# MF_badge_2021_protoshield_ver_A.net
KiCad netlist of a schematic drawn in EAGLE
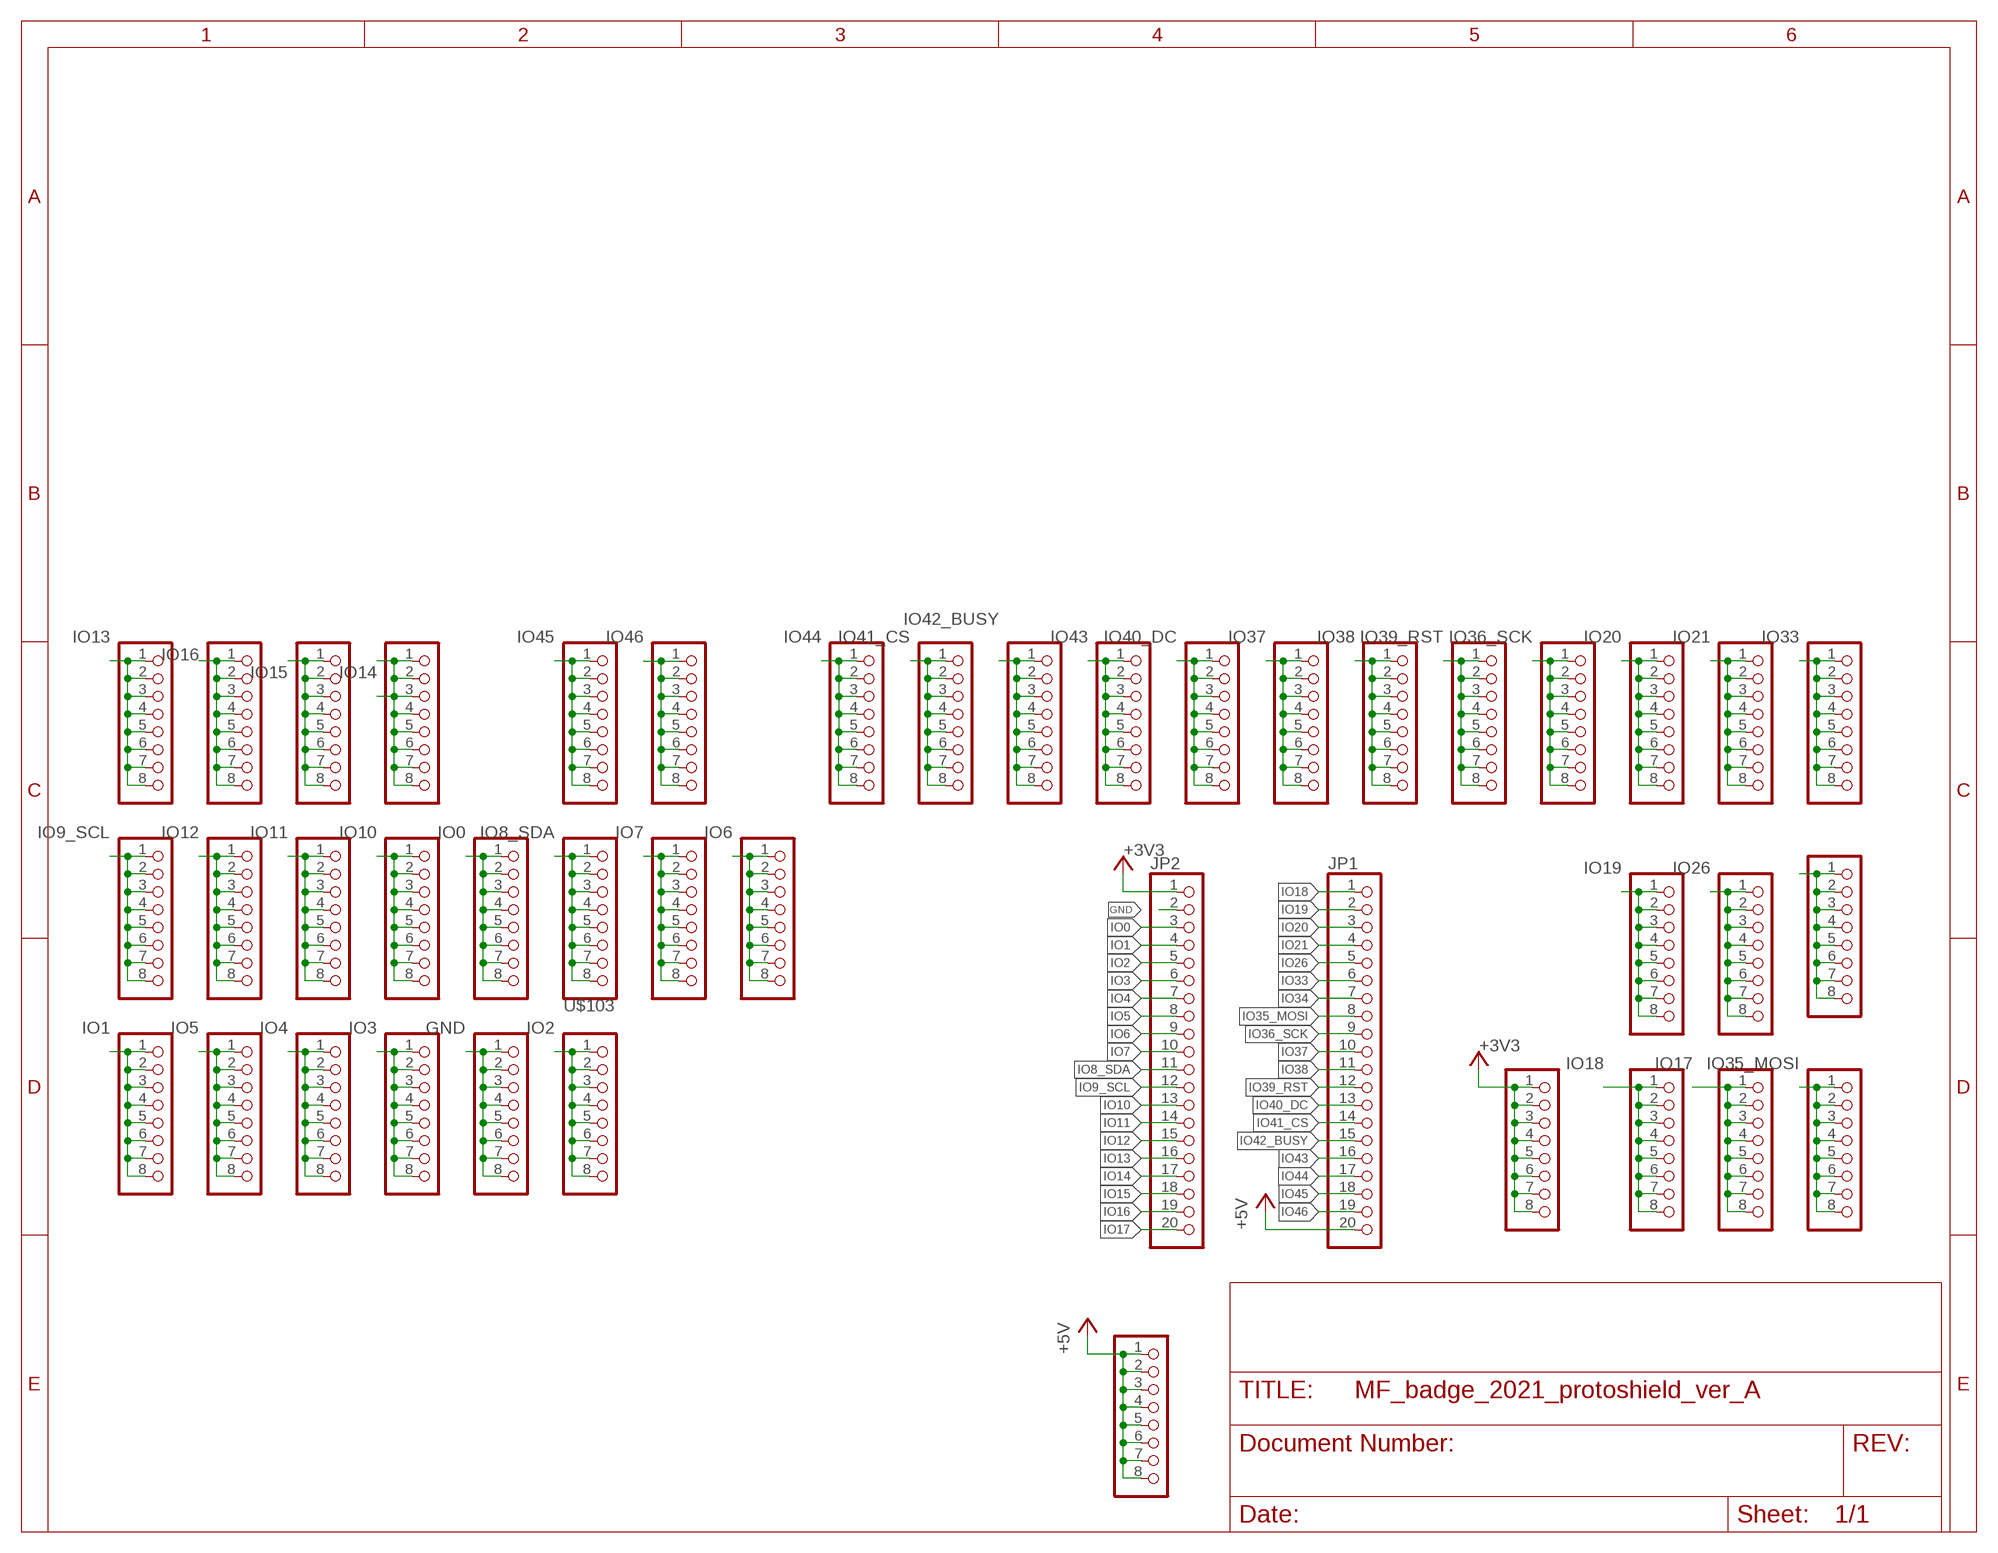
[diagram p0: schematic, sheet 1]

(export (version "E")
  (design (tool "Eeschema 10.0.6"))
  (components
    (comp (ref "JP1")
      (value "PINHD-1X20_CLEANBIG")
      (footprint "eagle-import:1X20-CLEANBIG")
      (libsource (lib "eagle-import") (part "PINHD-1X20_CLEANBIG"))
    )
    (comp (ref "JP2")
      (value "PINHD-1X20_CLEANBIG")
      (footprint "eagle-import:1X20-CLEANBIG")
      (libsource (lib "eagle-import") (part "PINHD-1X20_CLEANBIG"))
    )
    (comp (ref "U$1")
      (value "PINHD-1X8CLEANBIG")
      (footprint "eagle-import:1X08-CLEANBIG")
      (libsource (lib "eagle-import") (part "PINHD-1X8CLEANBIG"))
    )
    (comp (ref "U$5")
      (value "PINHD-1X8CLEANBIG")
      (footprint "eagle-import:1X08-CLEANBIG")
      (libsource (lib "eagle-import") (part "PINHD-1X8CLEANBIG"))
    )
    (comp (ref "U$7")
      (value "PINHD-1X8CLEANBIG")
      (footprint "eagle-import:1X08-CLEANBIG")
      (libsource (lib "eagle-import") (part "PINHD-1X8CLEANBIG"))
    )
    (comp (ref "U$8")
      (value "PINHD-1X8CLEANBIG")
      (footprint "eagle-import:1X08-CLEANBIG")
      (libsource (lib "eagle-import") (part "PINHD-1X8CLEANBIG"))
    )
    (comp (ref "U$9")
      (value "PINHD-1X8CLEANBIG")
      (footprint "eagle-import:1X08-CLEANBIG")
      (libsource (lib "eagle-import") (part "PINHD-1X8CLEANBIG"))
    )
    (comp (ref "U$10")
      (value "PINHD-1X8CLEANBIG")
      (footprint "eagle-import:1X08-CLEANBIG")
      (libsource (lib "eagle-import") (part "PINHD-1X8CLEANBIG"))
    )
    (comp (ref "U$11")
      (value "PINHD-1X8CLEANBIG")
      (footprint "eagle-import:1X08-CLEANBIG")
      (libsource (lib "eagle-import") (part "PINHD-1X8CLEANBIG"))
    )
    (comp (ref "U$12")
      (value "PINHD-1X8CLEANBIG")
      (footprint "eagle-import:1X08-CLEANBIG")
      (libsource (lib "eagle-import") (part "PINHD-1X8CLEANBIG"))
    )
    (comp (ref "U$13")
      (value "PINHD-1X8CLEANBIG")
      (footprint "eagle-import:1X08-CLEANBIG")
      (libsource (lib "eagle-import") (part "PINHD-1X8CLEANBIG"))
    )
    (comp (ref "U$14")
      (value "PINHD-1X8CLEANBIG")
      (footprint "eagle-import:1X08-CLEANBIG")
      (libsource (lib "eagle-import") (part "PINHD-1X8CLEANBIG"))
    )
    (comp (ref "U$15")
      (value "PINHD-1X8CLEANBIG")
      (footprint "eagle-import:1X08-CLEANBIG")
      (libsource (lib "eagle-import") (part "PINHD-1X8CLEANBIG"))
    )
    (comp (ref "U$36")
      (value "PINHD-1X8CLEANBIG")
      (footprint "eagle-import:1X08-CLEANBIG")
      (libsource (lib "eagle-import") (part "PINHD-1X8CLEANBIG"))
    )
    (comp (ref "U$52")
      (value "PINHD-1X8CLEANBIG")
      (footprint "eagle-import:1X08-CLEANBIG")
      (libsource (lib "eagle-import") (part "PINHD-1X8CLEANBIG"))
    )
    (comp (ref "U$53")
      (value "PINHD-1X8CLEANBIG")
      (footprint "eagle-import:1X08-CLEANBIG")
      (libsource (lib "eagle-import") (part "PINHD-1X8CLEANBIG"))
    )
    (comp (ref "U$54")
      (value "PINHD-1X8CLEANBIG")
      (footprint "eagle-import:1X08-CLEANBIG")
      (libsource (lib "eagle-import") (part "PINHD-1X8CLEANBIG"))
    )
    (comp (ref "U$55")
      (value "PINHD-1X8CLEANBIG")
      (footprint "eagle-import:1X08-CLEANBIG")
      (libsource (lib "eagle-import") (part "PINHD-1X8CLEANBIG"))
    )
    (comp (ref "U$56")
      (value "PINHD-1X8CLEANBIG")
      (footprint "eagle-import:1X08-CLEANBIG")
      (libsource (lib "eagle-import") (part "PINHD-1X8CLEANBIG"))
    )
    (comp (ref "U$61")
      (value "PINHD-1X8CLEANBIG")
      (footprint "eagle-import:1X08-CLEANBIG")
      (libsource (lib "eagle-import") (part "PINHD-1X8CLEANBIG"))
    )
    (comp (ref "U$62")
      (value "PINHD-1X8CLEANBIG")
      (footprint "eagle-import:1X08-CLEANBIG")
      (libsource (lib "eagle-import") (part "PINHD-1X8CLEANBIG"))
    )
    (comp (ref "U$63")
      (value "PINHD-1X8CLEANBIG")
      (footprint "eagle-import:1X08-CLEANBIG")
      (libsource (lib "eagle-import") (part "PINHD-1X8CLEANBIG"))
    )
    (comp (ref "U$64")
      (value "PINHD-1X8CLEANBIG")
      (footprint "eagle-import:1X08-CLEANBIG")
      (libsource (lib "eagle-import") (part "PINHD-1X8CLEANBIG"))
    )
    (comp (ref "U$102")
      (value "PINHD-1X8CLEANBIG")
      (footprint "eagle-import:1X08-CLEANBIG")
      (libsource (lib "eagle-import") (part "PINHD-1X8CLEANBIG"))
    )
    (comp (ref "U$103")
      (value "PINHD-1X8CLEANBIG")
      (footprint "eagle-import:1X08-CLEANBIG")
      (libsource (lib "eagle-import") (part "PINHD-1X8CLEANBIG"))
    )
    (comp (ref "U$104")
      (value "PINHD-1X8CLEANBIG")
      (footprint "eagle-import:1X08-CLEANBIG")
      (libsource (lib "eagle-import") (part "PINHD-1X8CLEANBIG"))
    )
    (comp (ref "U$105")
      (value "PINHD-1X8CLEANBIG")
      (footprint "eagle-import:1X08-CLEANBIG")
      (libsource (lib "eagle-import") (part "PINHD-1X8CLEANBIG"))
    )
    (comp (ref "U$106")
      (value "PINHD-1X8CLEANBIG")
      (footprint "eagle-import:1X08-CLEANBIG")
      (libsource (lib "eagle-import") (part "PINHD-1X8CLEANBIG"))
    )
    (comp (ref "U$107")
      (value "PINHD-1X8CLEANBIG")
      (footprint "eagle-import:1X08-CLEANBIG")
      (libsource (lib "eagle-import") (part "PINHD-1X8CLEANBIG"))
    )
    (comp (ref "U$108")
      (value "PINHD-1X8CLEANBIG")
      (footprint "eagle-import:1X08-CLEANBIG")
      (libsource (lib "eagle-import") (part "PINHD-1X8CLEANBIG"))
    )
    (comp (ref "U$109")
      (value "PINHD-1X8CLEANBIG")
      (footprint "eagle-import:1X08-CLEANBIG")
      (libsource (lib "eagle-import") (part "PINHD-1X8CLEANBIG"))
    )
    (comp (ref "U$110")
      (value "PINHD-1X8CLEANBIG")
      (footprint "eagle-import:1X08-CLEANBIG")
      (libsource (lib "eagle-import") (part "PINHD-1X8CLEANBIG"))
    )
    (comp (ref "U$111")
      (value "PINHD-1X8CLEANBIG")
      (footprint "eagle-import:1X08-CLEANBIG")
      (libsource (lib "eagle-import") (part "PINHD-1X8CLEANBIG"))
    )
    (comp (ref "U$112")
      (value "PINHD-1X8CLEANBIG")
      (footprint "eagle-import:1X08-CLEANBIG")
      (libsource (lib "eagle-import") (part "PINHD-1X8CLEANBIG"))
    )
    (comp (ref "U$113")
      (value "PINHD-1X8CLEANBIG")
      (footprint "eagle-import:1X08-CLEANBIG")
      (libsource (lib "eagle-import") (part "PINHD-1X8CLEANBIG"))
    )
    (comp (ref "U$114")
      (value "PINHD-1X8CLEANBIG")
      (footprint "eagle-import:1X08-CLEANBIG")
      (libsource (lib "eagle-import") (part "PINHD-1X8CLEANBIG"))
    )
    (comp (ref "U$115")
      (value "PINHD-1X8CLEANBIG")
      (footprint "eagle-import:1X08-CLEANBIG")
      (libsource (lib "eagle-import") (part "PINHD-1X8CLEANBIG"))
    )
    (comp (ref "U$116")
      (value "PINHD-1X8CLEANBIG")
      (footprint "eagle-import:1X08-CLEANBIG")
      (libsource (lib "eagle-import") (part "PINHD-1X8CLEANBIG"))
    )
    (comp (ref "U$117")
      (value "PINHD-1X8CLEANBIG")
      (footprint "eagle-import:1X08-CLEANBIG")
      (libsource (lib "eagle-import") (part "PINHD-1X8CLEANBIG"))
    )
    (comp (ref "U$118")
      (value "PINHD-1X8CLEANBIG")
      (footprint "eagle-import:1X08-CLEANBIG")
      (libsource (lib "eagle-import") (part "PINHD-1X8CLEANBIG"))
    )
    (comp (ref "U$119")
      (value "PINHD-1X8CLEANBIG")
      (footprint "eagle-import:1X08-CLEANBIG")
      (libsource (lib "eagle-import") (part "PINHD-1X8CLEANBIG"))
    )
    (comp (ref "U$120")
      (value "PINHD-1X8CLEANBIG")
      (footprint "eagle-import:1X08-CLEANBIG")
      (libsource (lib "eagle-import") (part "PINHD-1X8CLEANBIG"))
    )
  )
  (nets
    (net (code "1") (name "+3V3") (class "Default")
      (node (ref "JP2") (pin "1") (pinfunction "1_1") (pintype "passive"))
      (node (ref "U$1") (pin "1") (pinfunction "1_1") (pintype "passive"))
      (node (ref "U$1") (pin "2") (pinfunction "2_2") (pintype "passive"))
      (node (ref "U$1") (pin "3") (pinfunction "3_3") (pintype "passive"))
      (node (ref "U$1") (pin "4") (pinfunction "4_4") (pintype "passive"))
      (node (ref "U$1") (pin "5") (pinfunction "5_5") (pintype "passive"))
      (node (ref "U$1") (pin "6") (pinfunction "6_6") (pintype "passive"))
      (node (ref "U$1") (pin "7") (pinfunction "7_7") (pintype "passive"))
      (node (ref "U$1") (pin "8") (pinfunction "8_8") (pintype "passive"))
    )
    (net (code "2") (name "+5V") (class "Default")
      (node (ref "JP1") (pin "20") (pinfunction "20_20") (pintype "passive"))
      (node (ref "U$102") (pin "1") (pinfunction "1_1") (pintype "passive"))
      (node (ref "U$102") (pin "2") (pinfunction "2_2") (pintype "passive"))
      (node (ref "U$102") (pin "3") (pinfunction "3_3") (pintype "passive"))
      (node (ref "U$102") (pin "4") (pinfunction "4_4") (pintype "passive"))
      (node (ref "U$102") (pin "5") (pinfunction "5_5") (pintype "passive"))
      (node (ref "U$102") (pin "6") (pinfunction "6_6") (pintype "passive"))
      (node (ref "U$102") (pin "7") (pinfunction "7_7") (pintype "passive"))
      (node (ref "U$102") (pin "8") (pinfunction "8_8") (pintype "passive"))
    )
    (net (code "3") (name "GND") (class "Default")
      (node (ref "JP2") (pin "2") (pinfunction "2_2") (pintype "passive"))
      (node (ref "U$120") (pin "1") (pinfunction "1_1") (pintype "passive"))
      (node (ref "U$120") (pin "2") (pinfunction "2_2") (pintype "passive"))
      (node (ref "U$120") (pin "3") (pinfunction "3_3") (pintype "passive"))
      (node (ref "U$120") (pin "4") (pinfunction "4_4") (pintype "passive"))
      (node (ref "U$120") (pin "5") (pinfunction "5_5") (pintype "passive"))
      (node (ref "U$120") (pin "6") (pinfunction "6_6") (pintype "passive"))
      (node (ref "U$120") (pin "7") (pinfunction "7_7") (pintype "passive"))
      (node (ref "U$120") (pin "8") (pinfunction "8_8") (pintype "passive"))
    )
    (net (code "4") (name "IO0") (class "Default")
      (node (ref "JP2") (pin "3") (pinfunction "3_3") (pintype "passive"))
      (node (ref "U$115") (pin "1") (pinfunction "1_1") (pintype "passive"))
      (node (ref "U$115") (pin "2") (pinfunction "2_2") (pintype "passive"))
      (node (ref "U$115") (pin "3") (pinfunction "3_3") (pintype "passive"))
      (node (ref "U$115") (pin "4") (pinfunction "4_4") (pintype "passive"))
      (node (ref "U$115") (pin "5") (pinfunction "5_5") (pintype "passive"))
      (node (ref "U$115") (pin "6") (pinfunction "6_6") (pintype "passive"))
      (node (ref "U$115") (pin "7") (pinfunction "7_7") (pintype "passive"))
      (node (ref "U$115") (pin "8") (pinfunction "8_8") (pintype "passive"))
    )
    (net (code "5") (name "IO1") (class "Default")
      (node (ref "JP2") (pin "4") (pinfunction "4_4") (pintype "passive"))
      (node (ref "U$119") (pin "1") (pinfunction "1_1") (pintype "passive"))
      (node (ref "U$119") (pin "2") (pinfunction "2_2") (pintype "passive"))
      (node (ref "U$119") (pin "3") (pinfunction "3_3") (pintype "passive"))
      (node (ref "U$119") (pin "4") (pinfunction "4_4") (pintype "passive"))
      (node (ref "U$119") (pin "5") (pinfunction "5_5") (pintype "passive"))
      (node (ref "U$119") (pin "6") (pinfunction "6_6") (pintype "passive"))
      (node (ref "U$119") (pin "7") (pinfunction "7_7") (pintype "passive"))
      (node (ref "U$119") (pin "8") (pinfunction "8_8") (pintype "passive"))
    )
    (net (code "6") (name "IO2") (class "Default")
      (node (ref "JP2") (pin "5") (pinfunction "5_5") (pintype "passive"))
      (node (ref "U$103") (pin "1") (pinfunction "1_1") (pintype "passive"))
      (node (ref "U$103") (pin "2") (pinfunction "2_2") (pintype "passive"))
      (node (ref "U$103") (pin "3") (pinfunction "3_3") (pintype "passive"))
      (node (ref "U$103") (pin "4") (pinfunction "4_4") (pintype "passive"))
      (node (ref "U$103") (pin "5") (pinfunction "5_5") (pintype "passive"))
      (node (ref "U$103") (pin "6") (pinfunction "6_6") (pintype "passive"))
      (node (ref "U$103") (pin "7") (pinfunction "7_7") (pintype "passive"))
      (node (ref "U$103") (pin "8") (pinfunction "8_8") (pintype "passive"))
    )
    (net (code "7") (name "IO3") (class "Default")
      (node (ref "JP2") (pin "6") (pinfunction "6_6") (pintype "passive"))
      (node (ref "U$118") (pin "1") (pinfunction "1_1") (pintype "passive"))
      (node (ref "U$118") (pin "2") (pinfunction "2_2") (pintype "passive"))
      (node (ref "U$118") (pin "3") (pinfunction "3_3") (pintype "passive"))
      (node (ref "U$118") (pin "4") (pinfunction "4_4") (pintype "passive"))
      (node (ref "U$118") (pin "5") (pinfunction "5_5") (pintype "passive"))
      (node (ref "U$118") (pin "6") (pinfunction "6_6") (pintype "passive"))
      (node (ref "U$118") (pin "7") (pinfunction "7_7") (pintype "passive"))
      (node (ref "U$118") (pin "8") (pinfunction "8_8") (pintype "passive"))
    )
    (net (code "8") (name "IO4") (class "Default")
      (node (ref "JP2") (pin "7") (pinfunction "7_7") (pintype "passive"))
      (node (ref "U$117") (pin "1") (pinfunction "1_1") (pintype "passive"))
      (node (ref "U$117") (pin "2") (pinfunction "2_2") (pintype "passive"))
      (node (ref "U$117") (pin "3") (pinfunction "3_3") (pintype "passive"))
      (node (ref "U$117") (pin "4") (pinfunction "4_4") (pintype "passive"))
      (node (ref "U$117") (pin "5") (pinfunction "5_5") (pintype "passive"))
      (node (ref "U$117") (pin "6") (pinfunction "6_6") (pintype "passive"))
      (node (ref "U$117") (pin "7") (pinfunction "7_7") (pintype "passive"))
      (node (ref "U$117") (pin "8") (pinfunction "8_8") (pintype "passive"))
    )
    (net (code "9") (name "IO5") (class "Default")
      (node (ref "JP2") (pin "8") (pinfunction "8_8") (pintype "passive"))
      (node (ref "U$116") (pin "1") (pinfunction "1_1") (pintype "passive"))
      (node (ref "U$116") (pin "2") (pinfunction "2_2") (pintype "passive"))
      (node (ref "U$116") (pin "3") (pinfunction "3_3") (pintype "passive"))
      (node (ref "U$116") (pin "4") (pinfunction "4_4") (pintype "passive"))
      (node (ref "U$116") (pin "5") (pinfunction "5_5") (pintype "passive"))
      (node (ref "U$116") (pin "6") (pinfunction "6_6") (pintype "passive"))
      (node (ref "U$116") (pin "7") (pinfunction "7_7") (pintype "passive"))
      (node (ref "U$116") (pin "8") (pinfunction "8_8") (pintype "passive"))
    )
    (net (code "10") (name "IO6") (class "Default")
      (node (ref "JP2") (pin "9") (pinfunction "9_9") (pintype "passive"))
      (node (ref "U$114") (pin "1") (pinfunction "1_1") (pintype "passive"))
      (node (ref "U$114") (pin "2") (pinfunction "2_2") (pintype "passive"))
      (node (ref "U$114") (pin "3") (pinfunction "3_3") (pintype "passive"))
      (node (ref "U$114") (pin "4") (pinfunction "4_4") (pintype "passive"))
      (node (ref "U$114") (pin "5") (pinfunction "5_5") (pintype "passive"))
      (node (ref "U$114") (pin "6") (pinfunction "6_6") (pintype "passive"))
      (node (ref "U$114") (pin "7") (pinfunction "7_7") (pintype "passive"))
      (node (ref "U$114") (pin "8") (pinfunction "8_8") (pintype "passive"))
    )
    (net (code "11") (name "IO7") (class "Default")
      (node (ref "JP2") (pin "10") (pinfunction "10_10") (pintype "passive"))
      (node (ref "U$113") (pin "1") (pinfunction "1_1") (pintype "passive"))
      (node (ref "U$113") (pin "2") (pinfunction "2_2") (pintype "passive"))
      (node (ref "U$113") (pin "3") (pinfunction "3_3") (pintype "passive"))
      (node (ref "U$113") (pin "4") (pinfunction "4_4") (pintype "passive"))
      (node (ref "U$113") (pin "5") (pinfunction "5_5") (pintype "passive"))
      (node (ref "U$113") (pin "6") (pinfunction "6_6") (pintype "passive"))
      (node (ref "U$113") (pin "7") (pinfunction "7_7") (pintype "passive"))
      (node (ref "U$113") (pin "8") (pinfunction "8_8") (pintype "passive"))
    )
    (net (code "12") (name "IO8_SDA") (class "Default")
      (node (ref "JP2") (pin "11") (pinfunction "11_11") (pintype "passive"))
      (node (ref "U$112") (pin "1") (pinfunction "1_1") (pintype "passive"))
      (node (ref "U$112") (pin "2") (pinfunction "2_2") (pintype "passive"))
      (node (ref "U$112") (pin "3") (pinfunction "3_3") (pintype "passive"))
      (node (ref "U$112") (pin "4") (pinfunction "4_4") (pintype "passive"))
      (node (ref "U$112") (pin "5") (pinfunction "5_5") (pintype "passive"))
      (node (ref "U$112") (pin "6") (pinfunction "6_6") (pintype "passive"))
      (node (ref "U$112") (pin "7") (pinfunction "7_7") (pintype "passive"))
      (node (ref "U$112") (pin "8") (pinfunction "8_8") (pintype "passive"))
    )
    (net (code "13") (name "IO9_SCL") (class "Default")
      (node (ref "JP2") (pin "12") (pinfunction "12_12") (pintype "passive"))
      (node (ref "U$111") (pin "1") (pinfunction "1_1") (pintype "passive"))
      (node (ref "U$111") (pin "2") (pinfunction "2_2") (pintype "passive"))
      (node (ref "U$111") (pin "3") (pinfunction "3_3") (pintype "passive"))
      (node (ref "U$111") (pin "4") (pinfunction "4_4") (pintype "passive"))
      (node (ref "U$111") (pin "5") (pinfunction "5_5") (pintype "passive"))
      (node (ref "U$111") (pin "6") (pinfunction "6_6") (pintype "passive"))
      (node (ref "U$111") (pin "7") (pinfunction "7_7") (pintype "passive"))
      (node (ref "U$111") (pin "8") (pinfunction "8_8") (pintype "passive"))
    )
    (net (code "14") (name "IO10") (class "Default")
      (node (ref "JP2") (pin "13") (pinfunction "13_13") (pintype "passive"))
      (node (ref "U$110") (pin "1") (pinfunction "1_1") (pintype "passive"))
      (node (ref "U$110") (pin "2") (pinfunction "2_2") (pintype "passive"))
      (node (ref "U$110") (pin "3") (pinfunction "3_3") (pintype "passive"))
      (node (ref "U$110") (pin "4") (pinfunction "4_4") (pintype "passive"))
      (node (ref "U$110") (pin "5") (pinfunction "5_5") (pintype "passive"))
      (node (ref "U$110") (pin "6") (pinfunction "6_6") (pintype "passive"))
      (node (ref "U$110") (pin "7") (pinfunction "7_7") (pintype "passive"))
      (node (ref "U$110") (pin "8") (pinfunction "8_8") (pintype "passive"))
    )
    (net (code "15") (name "IO11") (class "Default")
      (node (ref "JP2") (pin "14") (pinfunction "14_14") (pintype "passive"))
      (node (ref "U$109") (pin "1") (pinfunction "1_1") (pintype "passive"))
      (node (ref "U$109") (pin "2") (pinfunction "2_2") (pintype "passive"))
      (node (ref "U$109") (pin "3") (pinfunction "3_3") (pintype "passive"))
      (node (ref "U$109") (pin "4") (pinfunction "4_4") (pintype "passive"))
      (node (ref "U$109") (pin "5") (pinfunction "5_5") (pintype "passive"))
      (node (ref "U$109") (pin "6") (pinfunction "6_6") (pintype "passive"))
      (node (ref "U$109") (pin "7") (pinfunction "7_7") (pintype "passive"))
      (node (ref "U$109") (pin "8") (pinfunction "8_8") (pintype "passive"))
    )
    (net (code "16") (name "IO12") (class "Default")
      (node (ref "JP2") (pin "15") (pinfunction "15_15") (pintype "passive"))
      (node (ref "U$108") (pin "1") (pinfunction "1_1") (pintype "passive"))
      (node (ref "U$108") (pin "2") (pinfunction "2_2") (pintype "passive"))
      (node (ref "U$108") (pin "3") (pinfunction "3_3") (pintype "passive"))
      (node (ref "U$108") (pin "4") (pinfunction "4_4") (pintype "passive"))
      (node (ref "U$108") (pin "5") (pinfunction "5_5") (pintype "passive"))
      (node (ref "U$108") (pin "6") (pinfunction "6_6") (pintype "passive"))
      (node (ref "U$108") (pin "7") (pinfunction "7_7") (pintype "passive"))
      (node (ref "U$108") (pin "8") (pinfunction "8_8") (pintype "passive"))
    )
    (net (code "17") (name "IO13") (class "Default")
      (node (ref "JP2") (pin "16") (pinfunction "16_16") (pintype "passive"))
      (node (ref "U$107") (pin "1") (pinfunction "1_1") (pintype "passive"))
      (node (ref "U$107") (pin "2") (pinfunction "2_2") (pintype "passive"))
      (node (ref "U$107") (pin "3") (pinfunction "3_3") (pintype "passive"))
      (node (ref "U$107") (pin "4") (pinfunction "4_4") (pintype "passive"))
      (node (ref "U$107") (pin "5") (pinfunction "5_5") (pintype "passive"))
      (node (ref "U$107") (pin "6") (pinfunction "6_6") (pintype "passive"))
      (node (ref "U$107") (pin "7") (pinfunction "7_7") (pintype "passive"))
      (node (ref "U$107") (pin "8") (pinfunction "8_8") (pintype "passive"))
    )
    (net (code "18") (name "IO14") (class "Default")
      (node (ref "JP2") (pin "17") (pinfunction "17_17") (pintype "passive"))
      (node (ref "U$106") (pin "1") (pinfunction "1_1") (pintype "passive"))
      (node (ref "U$106") (pin "2") (pinfunction "2_2") (pintype "passive"))
      (node (ref "U$106") (pin "3") (pinfunction "3_3") (pintype "passive"))
      (node (ref "U$106") (pin "4") (pinfunction "4_4") (pintype "passive"))
      (node (ref "U$106") (pin "5") (pinfunction "5_5") (pintype "passive"))
      (node (ref "U$106") (pin "6") (pinfunction "6_6") (pintype "passive"))
      (node (ref "U$106") (pin "7") (pinfunction "7_7") (pintype "passive"))
      (node (ref "U$106") (pin "8") (pinfunction "8_8") (pintype "passive"))
    )
    (net (code "19") (name "IO15") (class "Default")
      (node (ref "JP2") (pin "18") (pinfunction "18_18") (pintype "passive"))
      (node (ref "U$105") (pin "1") (pinfunction "1_1") (pintype "passive"))
      (node (ref "U$105") (pin "2") (pinfunction "2_2") (pintype "passive"))
      (node (ref "U$105") (pin "3") (pinfunction "3_3") (pintype "passive"))
      (node (ref "U$105") (pin "4") (pinfunction "4_4") (pintype "passive"))
      (node (ref "U$105") (pin "5") (pinfunction "5_5") (pintype "passive"))
      (node (ref "U$105") (pin "6") (pinfunction "6_6") (pintype "passive"))
      (node (ref "U$105") (pin "7") (pinfunction "7_7") (pintype "passive"))
      (node (ref "U$105") (pin "8") (pinfunction "8_8") (pintype "passive"))
    )
    (net (code "20") (name "IO16") (class "Default")
      (node (ref "JP2") (pin "19") (pinfunction "19_19") (pintype "passive"))
      (node (ref "U$104") (pin "1") (pinfunction "1_1") (pintype "passive"))
      (node (ref "U$104") (pin "2") (pinfunction "2_2") (pintype "passive"))
      (node (ref "U$104") (pin "3") (pinfunction "3_3") (pintype "passive"))
      (node (ref "U$104") (pin "4") (pinfunction "4_4") (pintype "passive"))
      (node (ref "U$104") (pin "5") (pinfunction "5_5") (pintype "passive"))
      (node (ref "U$104") (pin "6") (pinfunction "6_6") (pintype "passive"))
      (node (ref "U$104") (pin "7") (pinfunction "7_7") (pintype "passive"))
      (node (ref "U$104") (pin "8") (pinfunction "8_8") (pintype "passive"))
    )
    (net (code "21") (name "IO17") (class "Default")
      (node (ref "JP2") (pin "20") (pinfunction "20_20") (pintype "passive"))
      (node (ref "U$7") (pin "1") (pinfunction "1_1") (pintype "passive"))
      (node (ref "U$7") (pin "2") (pinfunction "2_2") (pintype "passive"))
      (node (ref "U$7") (pin "3") (pinfunction "3_3") (pintype "passive"))
      (node (ref "U$7") (pin "4") (pinfunction "4_4") (pintype "passive"))
      (node (ref "U$7") (pin "5") (pinfunction "5_5") (pintype "passive"))
      (node (ref "U$7") (pin "6") (pinfunction "6_6") (pintype "passive"))
      (node (ref "U$7") (pin "7") (pinfunction "7_7") (pintype "passive"))
      (node (ref "U$7") (pin "8") (pinfunction "8_8") (pintype "passive"))
    )
    (net (code "22") (name "IO18") (class "Default")
      (node (ref "JP1") (pin "1") (pinfunction "1_1") (pintype "passive"))
      (node (ref "U$5") (pin "1") (pinfunction "1_1") (pintype "passive"))
      (node (ref "U$5") (pin "2") (pinfunction "2_2") (pintype "passive"))
      (node (ref "U$5") (pin "3") (pinfunction "3_3") (pintype "passive"))
      (node (ref "U$5") (pin "4") (pinfunction "4_4") (pintype "passive"))
      (node (ref "U$5") (pin "5") (pinfunction "5_5") (pintype "passive"))
      (node (ref "U$5") (pin "6") (pinfunction "6_6") (pintype "passive"))
      (node (ref "U$5") (pin "7") (pinfunction "7_7") (pintype "passive"))
      (node (ref "U$5") (pin "8") (pinfunction "8_8") (pintype "passive"))
    )
    (net (code "23") (name "IO19") (class "Default")
      (node (ref "JP1") (pin "2") (pinfunction "2_2") (pintype "passive"))
      (node (ref "U$8") (pin "1") (pinfunction "1_1") (pintype "passive"))
      (node (ref "U$8") (pin "2") (pinfunction "2_2") (pintype "passive"))
      (node (ref "U$8") (pin "3") (pinfunction "3_3") (pintype "passive"))
      (node (ref "U$8") (pin "4") (pinfunction "4_4") (pintype "passive"))
      (node (ref "U$8") (pin "5") (pinfunction "5_5") (pintype "passive"))
      (node (ref "U$8") (pin "6") (pinfunction "6_6") (pintype "passive"))
      (node (ref "U$8") (pin "7") (pinfunction "7_7") (pintype "passive"))
      (node (ref "U$8") (pin "8") (pinfunction "8_8") (pintype "passive"))
    )
    (net (code "24") (name "IO20") (class "Default")
      (node (ref "JP1") (pin "3") (pinfunction "3_3") (pintype "passive"))
      (node (ref "U$9") (pin "1") (pinfunction "1_1") (pintype "passive"))
      (node (ref "U$9") (pin "2") (pinfunction "2_2") (pintype "passive"))
      (node (ref "U$9") (pin "3") (pinfunction "3_3") (pintype "passive"))
      (node (ref "U$9") (pin "4") (pinfunction "4_4") (pintype "passive"))
      (node (ref "U$9") (pin "5") (pinfunction "5_5") (pintype "passive"))
      (node (ref "U$9") (pin "6") (pinfunction "6_6") (pintype "passive"))
      (node (ref "U$9") (pin "7") (pinfunction "7_7") (pintype "passive"))
      (node (ref "U$9") (pin "8") (pinfunction "8_8") (pintype "passive"))
    )
    (net (code "25") (name "IO21") (class "Default")
      (node (ref "JP1") (pin "4") (pinfunction "4_4") (pintype "passive"))
      (node (ref "U$10") (pin "1") (pinfunction "1_1") (pintype "passive"))
      (node (ref "U$10") (pin "2") (pinfunction "2_2") (pintype "passive"))
      (node (ref "U$10") (pin "3") (pinfunction "3_3") (pintype "passive"))
      (node (ref "U$10") (pin "4") (pinfunction "4_4") (pintype "passive"))
      (node (ref "U$10") (pin "5") (pinfunction "5_5") (pintype "passive"))
      (node (ref "U$10") (pin "6") (pinfunction "6_6") (pintype "passive"))
      (node (ref "U$10") (pin "7") (pinfunction "7_7") (pintype "passive"))
      (node (ref "U$10") (pin "8") (pinfunction "8_8") (pintype "passive"))
    )
    (net (code "26") (name "IO26") (class "Default")
      (node (ref "JP1") (pin "5") (pinfunction "5_5") (pintype "passive"))
      (node (ref "U$11") (pin "1") (pinfunction "1_1") (pintype "passive"))
      (node (ref "U$11") (pin "2") (pinfunction "2_2") (pintype "passive"))
      (node (ref "U$11") (pin "3") (pinfunction "3_3") (pintype "passive"))
      (node (ref "U$11") (pin "4") (pinfunction "4_4") (pintype "passive"))
      (node (ref "U$11") (pin "5") (pinfunction "5_5") (pintype "passive"))
      (node (ref "U$11") (pin "6") (pinfunction "6_6") (pintype "passive"))
      (node (ref "U$11") (pin "7") (pinfunction "7_7") (pintype "passive"))
      (node (ref "U$11") (pin "8") (pinfunction "8_8") (pintype "passive"))
    )
    (net (code "27") (name "IO33") (class "Default")
      (node (ref "JP1") (pin "6") (pinfunction "6_6") (pintype "passive"))
      (node (ref "U$12") (pin "1") (pinfunction "1_1") (pintype "passive"))
      (node (ref "U$12") (pin "2") (pinfunction "2_2") (pintype "passive"))
      (node (ref "U$12") (pin "3") (pinfunction "3_3") (pintype "passive"))
      (node (ref "U$12") (pin "4") (pinfunction "4_4") (pintype "passive"))
      (node (ref "U$12") (pin "5") (pinfunction "5_5") (pintype "passive"))
      (node (ref "U$12") (pin "6") (pinfunction "6_6") (pintype "passive"))
      (node (ref "U$12") (pin "7") (pinfunction "7_7") (pintype "passive"))
      (node (ref "U$12") (pin "8") (pinfunction "8_8") (pintype "passive"))
    )
    (net (code "28") (name "IO34") (class "Default")
      (node (ref "JP1") (pin "7") (pinfunction "7_7") (pintype "passive"))
      (node (ref "U$13") (pin "1") (pinfunction "1_1") (pintype "passive"))
      (node (ref "U$13") (pin "2") (pinfunction "2_2") (pintype "passive"))
      (node (ref "U$13") (pin "3") (pinfunction "3_3") (pintype "passive"))
      (node (ref "U$13") (pin "4") (pinfunction "4_4") (pintype "passive"))
      (node (ref "U$13") (pin "5") (pinfunction "5_5") (pintype "passive"))
      (node (ref "U$13") (pin "6") (pinfunction "6_6") (pintype "passive"))
      (node (ref "U$13") (pin "7") (pinfunction "7_7") (pintype "passive"))
      (node (ref "U$13") (pin "8") (pinfunction "8_8") (pintype "passive"))
    )
    (net (code "29") (name "IO35_MOSI") (class "Default")
      (node (ref "JP1") (pin "8") (pinfunction "8_8") (pintype "passive"))
      (node (ref "U$14") (pin "1") (pinfunction "1_1") (pintype "passive"))
      (node (ref "U$14") (pin "2") (pinfunction "2_2") (pintype "passive"))
      (node (ref "U$14") (pin "3") (pinfunction "3_3") (pintype "passive"))
      (node (ref "U$14") (pin "4") (pinfunction "4_4") (pintype "passive"))
      (node (ref "U$14") (pin "5") (pinfunction "5_5") (pintype "passive"))
      (node (ref "U$14") (pin "6") (pinfunction "6_6") (pintype "passive"))
      (node (ref "U$14") (pin "7") (pinfunction "7_7") (pintype "passive"))
      (node (ref "U$14") (pin "8") (pinfunction "8_8") (pintype "passive"))
    )
    (net (code "30") (name "IO36_SCK") (class "Default")
      (node (ref "JP1") (pin "9") (pinfunction "9_9") (pintype "passive"))
      (node (ref "U$15") (pin "1") (pinfunction "1_1") (pintype "passive"))
      (node (ref "U$15") (pin "2") (pinfunction "2_2") (pintype "passive"))
      (node (ref "U$15") (pin "3") (pinfunction "3_3") (pintype "passive"))
      (node (ref "U$15") (pin "4") (pinfunction "4_4") (pintype "passive"))
      (node (ref "U$15") (pin "5") (pinfunction "5_5") (pintype "passive"))
      (node (ref "U$15") (pin "6") (pinfunction "6_6") (pintype "passive"))
      (node (ref "U$15") (pin "7") (pinfunction "7_7") (pintype "passive"))
      (node (ref "U$15") (pin "8") (pinfunction "8_8") (pintype "passive"))
    )
    (net (code "31") (name "IO37") (class "Default")
      (node (ref "JP1") (pin "10") (pinfunction "10_10") (pintype "passive"))
      (node (ref "U$36") (pin "1") (pinfunction "1_1") (pintype "passive"))
      (node (ref "U$36") (pin "2") (pinfunction "2_2") (pintype "passive"))
      (node (ref "U$36") (pin "3") (pinfunction "3_3") (pintype "passive"))
      (node (ref "U$36") (pin "4") (pinfunction "4_4") (pintype "passive"))
      (node (ref "U$36") (pin "5") (pinfunction "5_5") (pintype "passive"))
      (node (ref "U$36") (pin "6") (pinfunction "6_6") (pintype "passive"))
      (node (ref "U$36") (pin "7") (pinfunction "7_7") (pintype "passive"))
      (node (ref "U$36") (pin "8") (pinfunction "8_8") (pintype "passive"))
    )
    (net (code "32") (name "IO38") (class "Default")
      (node (ref "JP1") (pin "11") (pinfunction "11_11") (pintype "passive"))
      (node (ref "U$52") (pin "1") (pinfunction "1_1") (pintype "passive"))
      (node (ref "U$52") (pin "2") (pinfunction "2_2") (pintype "passive"))
      (node (ref "U$52") (pin "3") (pinfunction "3_3") (pintype "passive"))
      (node (ref "U$52") (pin "4") (pinfunction "4_4") (pintype "passive"))
      (node (ref "U$52") (pin "5") (pinfunction "5_5") (pintype "passive"))
      (node (ref "U$52") (pin "6") (pinfunction "6_6") (pintype "passive"))
      (node (ref "U$52") (pin "7") (pinfunction "7_7") (pintype "passive"))
      (node (ref "U$52") (pin "8") (pinfunction "8_8") (pintype "passive"))
    )
    (net (code "33") (name "IO39_RST") (class "Default")
      (node (ref "JP1") (pin "12") (pinfunction "12_12") (pintype "passive"))
      (node (ref "U$53") (pin "1") (pinfunction "1_1") (pintype "passive"))
      (node (ref "U$53") (pin "2") (pinfunction "2_2") (pintype "passive"))
      (node (ref "U$53") (pin "3") (pinfunction "3_3") (pintype "passive"))
      (node (ref "U$53") (pin "4") (pinfunction "4_4") (pintype "passive"))
      (node (ref "U$53") (pin "5") (pinfunction "5_5") (pintype "passive"))
      (node (ref "U$53") (pin "6") (pinfunction "6_6") (pintype "passive"))
      (node (ref "U$53") (pin "7") (pinfunction "7_7") (pintype "passive"))
      (node (ref "U$53") (pin "8") (pinfunction "8_8") (pintype "passive"))
    )
    (net (code "34") (name "IO40_DC") (class "Default")
      (node (ref "JP1") (pin "13") (pinfunction "13_13") (pintype "passive"))
      (node (ref "U$54") (pin "1") (pinfunction "1_1") (pintype "passive"))
      (node (ref "U$54") (pin "2") (pinfunction "2_2") (pintype "passive"))
      (node (ref "U$54") (pin "3") (pinfunction "3_3") (pintype "passive"))
      (node (ref "U$54") (pin "4") (pinfunction "4_4") (pintype "passive"))
      (node (ref "U$54") (pin "5") (pinfunction "5_5") (pintype "passive"))
      (node (ref "U$54") (pin "6") (pinfunction "6_6") (pintype "passive"))
      (node (ref "U$54") (pin "7") (pinfunction "7_7") (pintype "passive"))
      (node (ref "U$54") (pin "8") (pinfunction "8_8") (pintype "passive"))
    )
    (net (code "35") (name "IO41_CS") (class "Default")
      (node (ref "JP1") (pin "14") (pinfunction "14_14") (pintype "passive"))
      (node (ref "U$55") (pin "1") (pinfunction "1_1") (pintype "passive"))
      (node (ref "U$55") (pin "2") (pinfunction "2_2") (pintype "passive"))
      (node (ref "U$55") (pin "3") (pinfunction "3_3") (pintype "passive"))
      (node (ref "U$55") (pin "4") (pinfunction "4_4") (pintype "passive"))
      (node (ref "U$55") (pin "5") (pinfunction "5_5") (pintype "passive"))
      (node (ref "U$55") (pin "6") (pinfunction "6_6") (pintype "passive"))
      (node (ref "U$55") (pin "7") (pinfunction "7_7") (pintype "passive"))
      (node (ref "U$55") (pin "8") (pinfunction "8_8") (pintype "passive"))
    )
    (net (code "36") (name "IO42_BUSY") (class "Default")
      (node (ref "JP1") (pin "15") (pinfunction "15_15") (pintype "passive"))
      (node (ref "U$56") (pin "1") (pinfunction "1_1") (pintype "passive"))
      (node (ref "U$56") (pin "2") (pinfunction "2_2") (pintype "passive"))
      (node (ref "U$56") (pin "3") (pinfunction "3_3") (pintype "passive"))
      (node (ref "U$56") (pin "4") (pinfunction "4_4") (pintype "passive"))
      (node (ref "U$56") (pin "5") (pinfunction "5_5") (pintype "passive"))
      (node (ref "U$56") (pin "6") (pinfunction "6_6") (pintype "passive"))
      (node (ref "U$56") (pin "7") (pinfunction "7_7") (pintype "passive"))
      (node (ref "U$56") (pin "8") (pinfunction "8_8") (pintype "passive"))
    )
    (net (code "37") (name "IO43") (class "Default")
      (node (ref "JP1") (pin "16") (pinfunction "16_16") (pintype "passive"))
      (node (ref "U$61") (pin "1") (pinfunction "1_1") (pintype "passive"))
      (node (ref "U$61") (pin "2") (pinfunction "2_2") (pintype "passive"))
      (node (ref "U$61") (pin "3") (pinfunction "3_3") (pintype "passive"))
      (node (ref "U$61") (pin "4") (pinfunction "4_4") (pintype "passive"))
      (node (ref "U$61") (pin "5") (pinfunction "5_5") (pintype "passive"))
      (node (ref "U$61") (pin "6") (pinfunction "6_6") (pintype "passive"))
      (node (ref "U$61") (pin "7") (pinfunction "7_7") (pintype "passive"))
      (node (ref "U$61") (pin "8") (pinfunction "8_8") (pintype "passive"))
    )
    (net (code "38") (name "IO44") (class "Default")
      (node (ref "JP1") (pin "17") (pinfunction "17_17") (pintype "passive"))
      (node (ref "U$62") (pin "1") (pinfunction "1_1") (pintype "passive"))
      (node (ref "U$62") (pin "2") (pinfunction "2_2") (pintype "passive"))
      (node (ref "U$62") (pin "3") (pinfunction "3_3") (pintype "passive"))
      (node (ref "U$62") (pin "4") (pinfunction "4_4") (pintype "passive"))
      (node (ref "U$62") (pin "5") (pinfunction "5_5") (pintype "passive"))
      (node (ref "U$62") (pin "6") (pinfunction "6_6") (pintype "passive"))
      (node (ref "U$62") (pin "7") (pinfunction "7_7") (pintype "passive"))
      (node (ref "U$62") (pin "8") (pinfunction "8_8") (pintype "passive"))
    )
    (net (code "39") (name "IO45") (class "Default")
      (node (ref "JP1") (pin "18") (pinfunction "18_18") (pintype "passive"))
      (node (ref "U$63") (pin "1") (pinfunction "1_1") (pintype "passive"))
      (node (ref "U$63") (pin "2") (pinfunction "2_2") (pintype "passive"))
      (node (ref "U$63") (pin "3") (pinfunction "3_3") (pintype "passive"))
      (node (ref "U$63") (pin "4") (pinfunction "4_4") (pintype "passive"))
      (node (ref "U$63") (pin "5") (pinfunction "5_5") (pintype "passive"))
      (node (ref "U$63") (pin "6") (pinfunction "6_6") (pintype "passive"))
      (node (ref "U$63") (pin "7") (pinfunction "7_7") (pintype "passive"))
      (node (ref "U$63") (pin "8") (pinfunction "8_8") (pintype "passive"))
    )
    (net (code "40") (name "IO46") (class "Default")
      (node (ref "JP1") (pin "19") (pinfunction "19_19") (pintype "passive"))
      (node (ref "U$64") (pin "1") (pinfunction "1_1") (pintype "passive"))
      (node (ref "U$64") (pin "2") (pinfunction "2_2") (pintype "passive"))
      (node (ref "U$64") (pin "3") (pinfunction "3_3") (pintype "passive"))
      (node (ref "U$64") (pin "4") (pinfunction "4_4") (pintype "passive"))
      (node (ref "U$64") (pin "5") (pinfunction "5_5") (pintype "passive"))
      (node (ref "U$64") (pin "6") (pinfunction "6_6") (pintype "passive"))
      (node (ref "U$64") (pin "7") (pinfunction "7_7") (pintype "passive"))
      (node (ref "U$64") (pin "8") (pinfunction "8_8") (pintype "passive"))
    )
  )
)
